# untitled_5.net
KiCad netlist of a schematic drawn in EAGLE
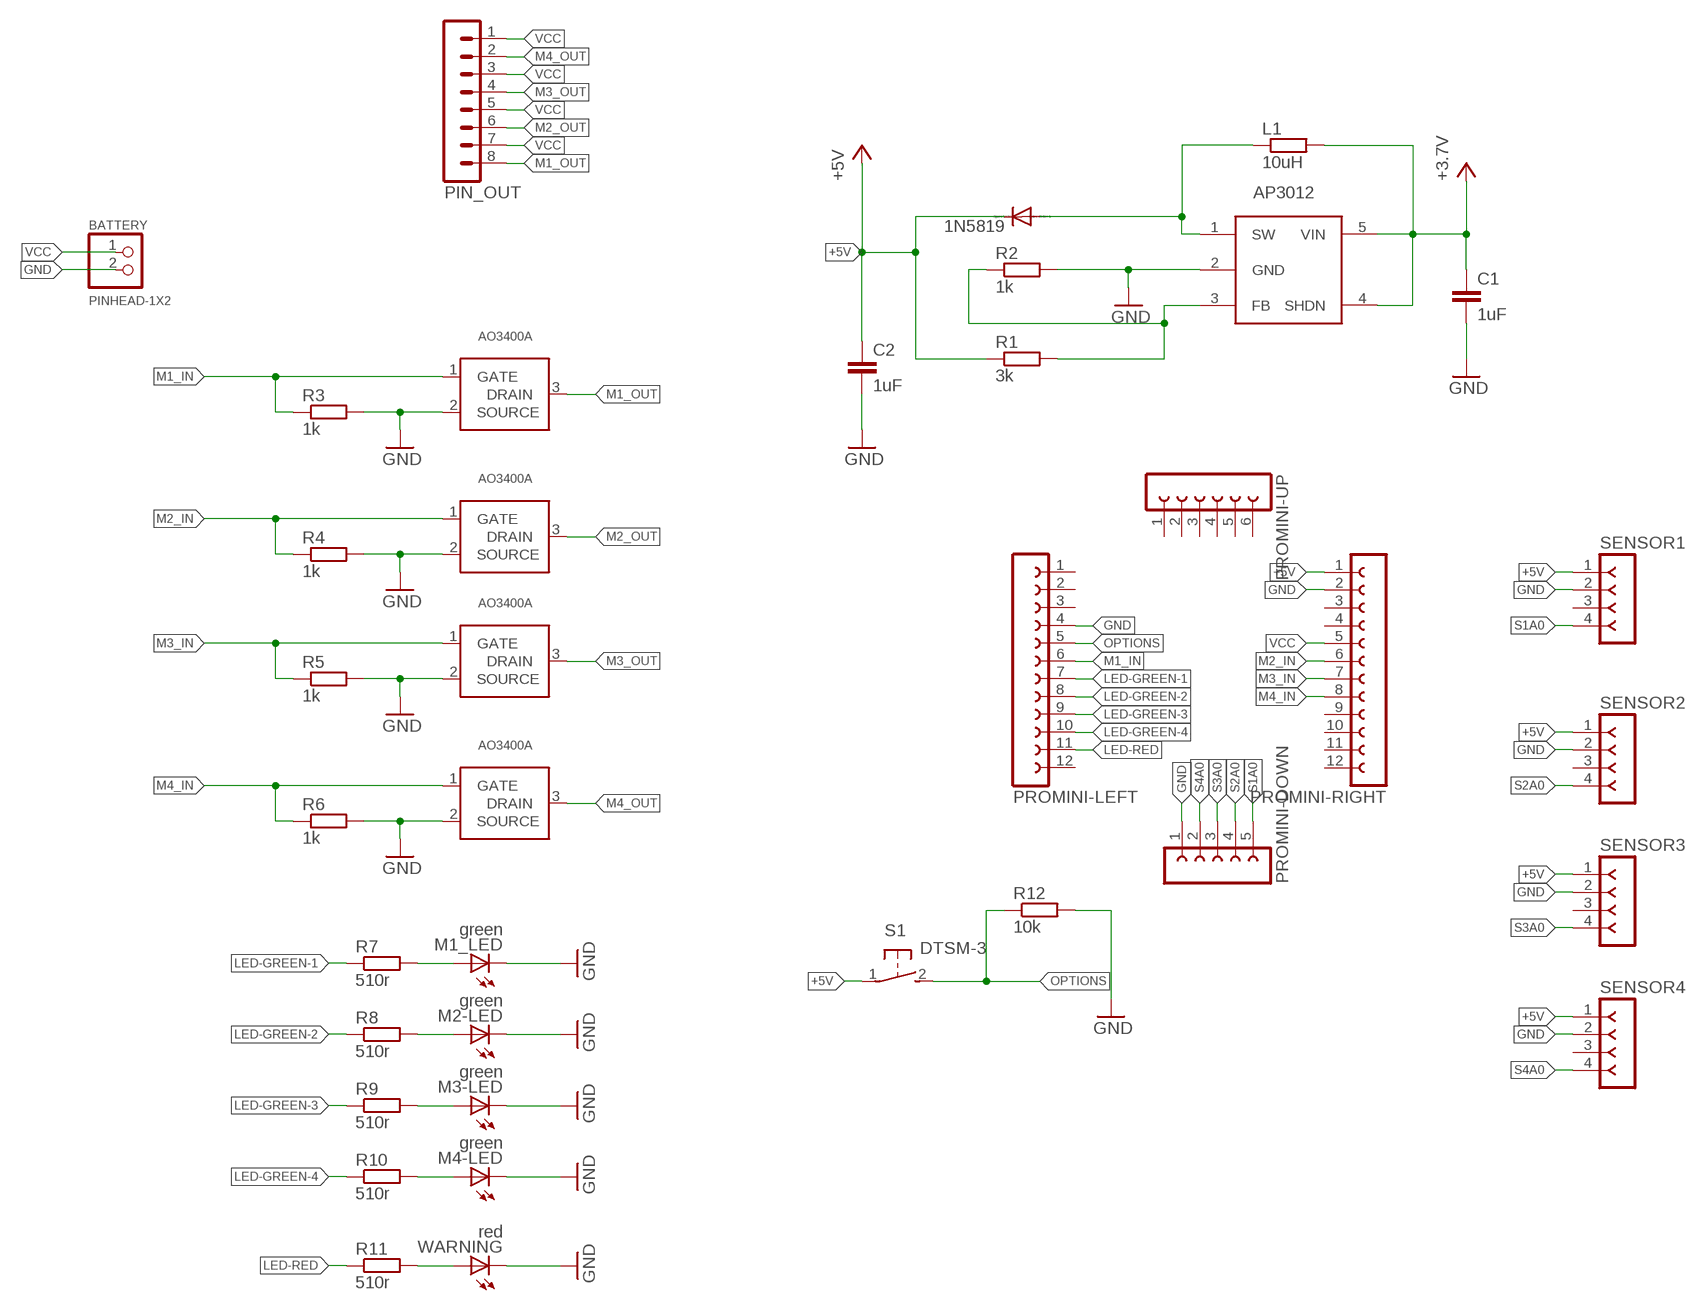
[diagram p0: schematic, sheet 1]

(export (version "E")
  (design (tool "Eeschema 10.0.6"))
  (components
    (comp (ref "1N5819")
      (value "DIODE-DO214AC")
      (footprint "eagle-import:DO214AC")
      (libsource (lib "eagle-import") (part "DIODE-DO214AC"))
    )
    (comp (ref "BATTERY")
      (value "PINHEAD-1X2")
      (footprint "eagle-import:PIHEAD-1X2")
      (libsource (lib "eagle-import") (part "PINHEAD-1X2"))
    )
    (comp (ref "C1")
      (value "1uF")
      (footprint "eagle-import:C1206")
      (libsource (lib "eagle-import") (part "C-EUC1206"))
    )
    (comp (ref "C2")
      (value "1uF")
      (footprint "eagle-import:C1206")
      (libsource (lib "eagle-import") (part "C-EUC1206"))
    )
    (comp (ref "L1")
      (value "10uH")
      (footprint "eagle-import:R0805")
      (libsource (lib "eagle-import") (part "R-EU_R0805"))
    )
    (comp (ref "M1_LED")
      (value "green")
      (footprint "eagle-import:CHIP-LED0805")
      (libsource (lib "eagle-import") (part "LEDCHIP-LED0805"))
    )
    (comp (ref "M2-LED")
      (value "green")
      (footprint "eagle-import:CHIP-LED0805")
      (libsource (lib "eagle-import") (part "LEDCHIP-LED0805"))
    )
    (comp (ref "M3-LED")
      (value "green")
      (footprint "eagle-import:CHIP-LED0805")
      (libsource (lib "eagle-import") (part "LEDCHIP-LED0805"))
    )
    (comp (ref "M4-LED")
      (value "green")
      (footprint "eagle-import:CHIP-LED0805")
      (libsource (lib "eagle-import") (part "LEDCHIP-LED0805"))
    )
    (comp (ref "MOSFET1")
      (value "AO3400A")
      (footprint "eagle-import:SOT-23")
      (libsource (lib "eagle-import") (part "AO3400A"))
    )
    (comp (ref "MOSFET2")
      (value "AO3400A")
      (footprint "eagle-import:SOT-23")
      (libsource (lib "eagle-import") (part "AO3400A"))
    )
    (comp (ref "MOSFET3")
      (value "AO3400A")
      (footprint "eagle-import:SOT-23")
      (libsource (lib "eagle-import") (part "AO3400A"))
    )
    (comp (ref "MOSFET4")
      (value "AO3400A")
      (footprint "eagle-import:SOT-23")
      (libsource (lib "eagle-import") (part "AO3400A"))
    )
    (comp (ref "PIN_OUT")
      (value "MA08-1")
      (footprint "eagle-import:MA08-1")
      (libsource (lib "eagle-import") (part "MA08-1"))
    )
    (comp (ref "PROMINI-DOWN")
      (value "FE05-1")
      (footprint "eagle-import:FE05-1")
      (libsource (lib "eagle-import") (part "FE05-1"))
    )
    (comp (ref "PROMINI-LEFT")
      (value "FE12-1")
      (footprint "eagle-import:FE12")
      (libsource (lib "eagle-import") (part "FE12-1"))
    )
    (comp (ref "PROMINI-RIGHT")
      (value "FE12-1")
      (footprint "eagle-import:FE12")
      (libsource (lib "eagle-import") (part "FE12-1"))
    )
    (comp (ref "PROMINI-UP")
      (value "FE06-1")
      (footprint "eagle-import:FE06")
      (libsource (lib "eagle-import") (part "FE06-1"))
    )
    (comp (ref "R1")
      (value "3k")
      (footprint "eagle-import:R1206")
      (libsource (lib "eagle-import") (part "R-EU_R1206"))
    )
    (comp (ref "R2")
      (value "1k")
      (footprint "eagle-import:R1206")
      (libsource (lib "eagle-import") (part "R-EU_R1206"))
    )
    (comp (ref "R3")
      (value "1k")
      (footprint "eagle-import:R1206")
      (libsource (lib "eagle-import") (part "R-EU_R1206"))
    )
    (comp (ref "R4")
      (value "1k")
      (footprint "eagle-import:R1206")
      (libsource (lib "eagle-import") (part "R-EU_R1206"))
    )
    (comp (ref "R5")
      (value "1k")
      (footprint "eagle-import:R1206")
      (libsource (lib "eagle-import") (part "R-EU_R1206"))
    )
    (comp (ref "R6")
      (value "1k")
      (footprint "eagle-import:R1206")
      (libsource (lib "eagle-import") (part "R-EU_R1206"))
    )
    (comp (ref "R7")
      (value "510r")
      (footprint "eagle-import:M0805")
      (libsource (lib "eagle-import") (part "R-EU_M0805"))
    )
    (comp (ref "R8")
      (value "510r")
      (footprint "eagle-import:M0805")
      (libsource (lib "eagle-import") (part "R-EU_M0805"))
    )
    (comp (ref "R9")
      (value "510r")
      (footprint "eagle-import:M0805")
      (libsource (lib "eagle-import") (part "R-EU_M0805"))
    )
    (comp (ref "R10")
      (value "510r")
      (footprint "eagle-import:M0805")
      (libsource (lib "eagle-import") (part "R-EU_M0805"))
    )
    (comp (ref "R11")
      (value "510r")
      (footprint "eagle-import:M0805")
      (libsource (lib "eagle-import") (part "R-EU_M0805"))
    )
    (comp (ref "R12")
      (value "10k")
      (footprint "eagle-import:R1206")
      (libsource (lib "eagle-import") (part "R-EU_R1206"))
    )
    (comp (ref "S1")
      (value "DTSM-3")
      (footprint "eagle-import:DTSM-3")
      (libsource (lib "eagle-import") (part "DTSM-3"))
    )
    (comp (ref "SENSOR1")
      (value "F-1X04-SIP-100-32Y")
      (footprint "eagle-import:SIP-100-04-32Y")
      (libsource (lib "eagle-import") (part "F-1X04-SIP-100-32Y"))
    )
    (comp (ref "SENSOR2")
      (value "F-1X04-SIP-100-32Y")
      (footprint "eagle-import:SIP-100-04-32Y")
      (libsource (lib "eagle-import") (part "F-1X04-SIP-100-32Y"))
    )
    (comp (ref "SENSOR3")
      (value "F-1X04-SIP-100-32Y")
      (footprint "eagle-import:SIP-100-04-32Y")
      (libsource (lib "eagle-import") (part "F-1X04-SIP-100-32Y"))
    )
    (comp (ref "SENSOR4")
      (value "F-1X04-SIP-100-32Y")
      (footprint "eagle-import:SIP-100-04-32Y")
      (libsource (lib "eagle-import") (part "F-1X04-SIP-100-32Y"))
    )
    (comp (ref "U$1")
      (value "AP3012")
      (footprint "eagle-import:SOT-23-5")
      (libsource (lib "eagle-import") (part "AP3012"))
    )
    (comp (ref "WARNING")
      (value "red")
      (footprint "eagle-import:CHIP-LED0805")
      (libsource (lib "eagle-import") (part "LEDCHIP-LED0805"))
    )
  )
  (nets
    (net (code "1") (name "+5V") (class "Default")
      (node (ref "1N5819") (pin "C") (pinfunction "C_C") (pintype "passive"))
      (node (ref "C2") (pin "1") (pinfunction "1_1") (pintype "passive"))
      (node (ref "PROMINI-RIGHT") (pin "1") (pinfunction "1_1") (pintype "passive"))
      (node (ref "R1") (pin "1") (pinfunction "1_1") (pintype "passive"))
      (node (ref "S1") (pin "1") (pinfunction "1_1") (pintype "passive"))
      (node (ref "SENSOR1") (pin "1") (pinfunction "1_1") (pintype "passive"))
      (node (ref "SENSOR2") (pin "1") (pinfunction "1_1") (pintype "passive"))
      (node (ref "SENSOR3") (pin "1") (pinfunction "1_1") (pintype "passive"))
      (node (ref "SENSOR4") (pin "1") (pinfunction "1_1") (pintype "passive"))
    )
    (net (code "2") (name "GND") (class "Default")
      (node (ref "BATTERY") (pin "2") (pinfunction "2_2") (pintype "passive"))
      (node (ref "C1") (pin "2") (pinfunction "2_2") (pintype "passive"))
      (node (ref "C2") (pin "2") (pinfunction "2_2") (pintype "passive"))
      (node (ref "M1_LED") (pin "C") (pinfunction "C_C") (pintype "passive"))
      (node (ref "M2-LED") (pin "C") (pinfunction "C_C") (pintype "passive"))
      (node (ref "M3-LED") (pin "C") (pinfunction "C_C") (pintype "passive"))
      (node (ref "M4-LED") (pin "C") (pinfunction "C_C") (pintype "passive"))
      (node (ref "MOSFET1") (pin "2") (pinfunction "SOURCE_2") (pintype "bidirectional"))
      (node (ref "MOSFET2") (pin "2") (pinfunction "SOURCE_2") (pintype "bidirectional"))
      (node (ref "MOSFET3") (pin "2") (pinfunction "SOURCE_2") (pintype "bidirectional"))
      (node (ref "MOSFET4") (pin "2") (pinfunction "SOURCE_2") (pintype "bidirectional"))
      (node (ref "PROMINI-DOWN") (pin "1") (pinfunction "1_1") (pintype "passive"))
      (node (ref "PROMINI-LEFT") (pin "4") (pinfunction "4_4") (pintype "passive"))
      (node (ref "PROMINI-RIGHT") (pin "2") (pinfunction "2_2") (pintype "passive"))
      (node (ref "R12") (pin "2") (pinfunction "2_2") (pintype "passive"))
      (node (ref "R2") (pin "2") (pinfunction "2_2") (pintype "passive"))
      (node (ref "R3") (pin "2") (pinfunction "2_2") (pintype "passive"))
      (node (ref "R4") (pin "2") (pinfunction "2_2") (pintype "passive"))
      (node (ref "R5") (pin "2") (pinfunction "2_2") (pintype "passive"))
      (node (ref "R6") (pin "2") (pinfunction "2_2") (pintype "passive"))
      (node (ref "SENSOR1") (pin "2") (pinfunction "2_2") (pintype "passive"))
      (node (ref "SENSOR2") (pin "2") (pinfunction "2_2") (pintype "passive"))
      (node (ref "SENSOR3") (pin "2") (pinfunction "2_2") (pintype "passive"))
      (node (ref "SENSOR4") (pin "2") (pinfunction "2_2") (pintype "passive"))
      (node (ref "U$1") (pin "2") (pinfunction "GND_2") (pintype "bidirectional"))
      (node (ref "WARNING") (pin "C") (pinfunction "C_C") (pintype "passive"))
    )
    (net (code "3") (name "LED-GREEN-1") (class "Default")
      (node (ref "PROMINI-LEFT") (pin "7") (pinfunction "7_7") (pintype "passive"))
      (node (ref "R7") (pin "1") (pinfunction "1_1") (pintype "passive"))
    )
    (net (code "4") (name "LED-GREEN-2") (class "Default")
      (node (ref "PROMINI-LEFT") (pin "8") (pinfunction "8_8") (pintype "passive"))
      (node (ref "R8") (pin "1") (pinfunction "1_1") (pintype "passive"))
    )
    (net (code "5") (name "LED-GREEN-3") (class "Default")
      (node (ref "PROMINI-LEFT") (pin "9") (pinfunction "9_9") (pintype "passive"))
      (node (ref "R9") (pin "1") (pinfunction "1_1") (pintype "passive"))
    )
    (net (code "6") (name "LED-GREEN-4") (class "Default")
      (node (ref "PROMINI-LEFT") (pin "10") (pinfunction "10_10") (pintype "passive"))
      (node (ref "R10") (pin "1") (pinfunction "1_1") (pintype "passive"))
    )
    (net (code "7") (name "LED-RED") (class "Default")
      (node (ref "PROMINI-LEFT") (pin "11") (pinfunction "11_11") (pintype "passive"))
      (node (ref "R11") (pin "1") (pinfunction "1_1") (pintype "passive"))
    )
    (net (code "8") (name "M1_IN") (class "Default")
      (node (ref "MOSFET1") (pin "1") (pinfunction "GATE_1") (pintype "bidirectional"))
      (node (ref "PROMINI-LEFT") (pin "6") (pinfunction "6_6") (pintype "passive"))
      (node (ref "R3") (pin "1") (pinfunction "1_1") (pintype "passive"))
    )
    (net (code "9") (name "M1_OUT") (class "Default")
      (node (ref "MOSFET1") (pin "3") (pinfunction "DRAIN_3") (pintype "bidirectional"))
      (node (ref "PIN_OUT") (pin "8") (pinfunction "8_8") (pintype "passive"))
    )
    (net (code "10") (name "M2_IN") (class "Default")
      (node (ref "MOSFET2") (pin "1") (pinfunction "GATE_1") (pintype "bidirectional"))
      (node (ref "PROMINI-RIGHT") (pin "6") (pinfunction "6_6") (pintype "passive"))
      (node (ref "R4") (pin "1") (pinfunction "1_1") (pintype "passive"))
    )
    (net (code "11") (name "M2_OUT") (class "Default")
      (node (ref "MOSFET2") (pin "3") (pinfunction "DRAIN_3") (pintype "bidirectional"))
      (node (ref "PIN_OUT") (pin "6") (pinfunction "6_6") (pintype "passive"))
    )
    (net (code "12") (name "M3_IN") (class "Default")
      (node (ref "MOSFET3") (pin "1") (pinfunction "GATE_1") (pintype "bidirectional"))
      (node (ref "PROMINI-RIGHT") (pin "7") (pinfunction "7_7") (pintype "passive"))
      (node (ref "R5") (pin "1") (pinfunction "1_1") (pintype "passive"))
    )
    (net (code "13") (name "M3_OUT") (class "Default")
      (node (ref "MOSFET3") (pin "3") (pinfunction "DRAIN_3") (pintype "bidirectional"))
      (node (ref "PIN_OUT") (pin "4") (pinfunction "4_4") (pintype "passive"))
    )
    (net (code "14") (name "M4_IN") (class "Default")
      (node (ref "MOSFET4") (pin "1") (pinfunction "GATE_1") (pintype "bidirectional"))
      (node (ref "PROMINI-RIGHT") (pin "8") (pinfunction "8_8") (pintype "passive"))
      (node (ref "R6") (pin "1") (pinfunction "1_1") (pintype "passive"))
    )
    (net (code "15") (name "M4_OUT") (class "Default")
      (node (ref "MOSFET4") (pin "3") (pinfunction "DRAIN_3") (pintype "bidirectional"))
      (node (ref "PIN_OUT") (pin "2") (pinfunction "2_2") (pintype "passive"))
    )
    (net (code "16") (name "Net-(M1_LED-PadA)") (class "Default")
      (node (ref "M1_LED") (pin "A") (pinfunction "A_A") (pintype "passive"))
      (node (ref "R7") (pin "2") (pinfunction "2_2") (pintype "passive"))
    )
    (net (code "17") (name "Net-(M2-LED-PadA)") (class "Default")
      (node (ref "M2-LED") (pin "A") (pinfunction "A_A") (pintype "passive"))
      (node (ref "R8") (pin "2") (pinfunction "2_2") (pintype "passive"))
    )
    (net (code "18") (name "Net-(M3-LED-PadA)") (class "Default")
      (node (ref "M3-LED") (pin "A") (pinfunction "A_A") (pintype "passive"))
      (node (ref "R9") (pin "2") (pinfunction "2_2") (pintype "passive"))
    )
    (net (code "19") (name "Net-(M4-LED-PadA)") (class "Default")
      (node (ref "M4-LED") (pin "A") (pinfunction "A_A") (pintype "passive"))
      (node (ref "R10") (pin "2") (pinfunction "2_2") (pintype "passive"))
    )
    (net (code "20") (name "Net-(R11-Pad2)") (class "Default")
      (node (ref "R11") (pin "2") (pinfunction "2_2") (pintype "passive"))
      (node (ref "WARNING") (pin "A") (pinfunction "A_A") (pintype "passive"))
    )
    (net (code "21") (name "Net-(U$1-FB)") (class "Default")
      (node (ref "R1") (pin "2") (pinfunction "2_2") (pintype "passive"))
      (node (ref "R2") (pin "1") (pinfunction "1_1") (pintype "passive"))
      (node (ref "U$1") (pin "3") (pinfunction "FB_3") (pintype "bidirectional"))
    )
    (net (code "22") (name "Net-(U$1-SW)") (class "Default")
      (node (ref "1N5819") (pin "A") (pinfunction "A_A") (pintype "passive"))
      (node (ref "L1") (pin "1") (pinfunction "1_1") (pintype "passive"))
      (node (ref "U$1") (pin "1") (pinfunction "SW_1") (pintype "bidirectional"))
    )
    (net (code "23") (name "OPTIONS") (class "Default")
      (node (ref "PROMINI-LEFT") (pin "5") (pinfunction "5_5") (pintype "passive"))
      (node (ref "R12") (pin "1") (pinfunction "1_1") (pintype "passive"))
      (node (ref "S1") (pin "2") (pinfunction "2_2") (pintype "passive"))
    )
    (net (code "24") (name "S1A0") (class "Default")
      (node (ref "PROMINI-DOWN") (pin "5") (pinfunction "5_5") (pintype "passive"))
      (node (ref "SENSOR1") (pin "4") (pinfunction "4_4") (pintype "passive"))
    )
    (net (code "25") (name "S2A0") (class "Default")
      (node (ref "PROMINI-DOWN") (pin "4") (pinfunction "4_4") (pintype "passive"))
      (node (ref "SENSOR2") (pin "4") (pinfunction "4_4") (pintype "passive"))
    )
    (net (code "26") (name "S3A0") (class "Default")
      (node (ref "PROMINI-DOWN") (pin "3") (pinfunction "3_3") (pintype "passive"))
      (node (ref "SENSOR3") (pin "4") (pinfunction "4_4") (pintype "passive"))
    )
    (net (code "27") (name "S4A0") (class "Default")
      (node (ref "PROMINI-DOWN") (pin "2") (pinfunction "2_2") (pintype "passive"))
      (node (ref "SENSOR4") (pin "4") (pinfunction "4_4") (pintype "passive"))
    )
    (net (code "28") (name "VCC") (class "Default")
      (node (ref "BATTERY") (pin "1") (pinfunction "1_1") (pintype "passive"))
      (node (ref "C1") (pin "1") (pinfunction "1_1") (pintype "passive"))
      (node (ref "L1") (pin "2") (pinfunction "2_2") (pintype "passive"))
      (node (ref "PIN_OUT") (pin "1") (pinfunction "1_1") (pintype "passive"))
      (node (ref "PIN_OUT") (pin "3") (pinfunction "3_3") (pintype "passive"))
      (node (ref "PIN_OUT") (pin "5") (pinfunction "5_5") (pintype "passive"))
      (node (ref "PIN_OUT") (pin "7") (pinfunction "7_7") (pintype "passive"))
      (node (ref "PROMINI-RIGHT") (pin "5") (pinfunction "5_5") (pintype "passive"))
      (node (ref "U$1") (pin "4") (pinfunction "SHDN_4") (pintype "bidirectional"))
      (node (ref "U$1") (pin "5") (pinfunction "VIN_5") (pintype "bidirectional"))
    )
    (net (code "29") (name "unconnected-(PROMINI-LEFT-Pad1)") (class "Default")
      (node (ref "PROMINI-LEFT") (pin "1") (pinfunction "1_1") (pintype "passive"))
    )
    (net (code "30") (name "unconnected-(PROMINI-LEFT-Pad2)") (class "Default")
      (node (ref "PROMINI-LEFT") (pin "2") (pinfunction "2_2") (pintype "passive"))
    )
    (net (code "31") (name "unconnected-(PROMINI-LEFT-Pad3)") (class "Default")
      (node (ref "PROMINI-LEFT") (pin "3") (pinfunction "3_3") (pintype "passive"))
    )
    (net (code "32") (name "unconnected-(PROMINI-LEFT-Pad12)") (class "Default")
      (node (ref "PROMINI-LEFT") (pin "12") (pinfunction "12_12") (pintype "passive"))
    )
    (net (code "33") (name "unconnected-(PROMINI-RIGHT-Pad3)") (class "Default")
      (node (ref "PROMINI-RIGHT") (pin "3") (pinfunction "3_3") (pintype "passive"))
    )
    (net (code "34") (name "unconnected-(PROMINI-RIGHT-Pad4)") (class "Default")
      (node (ref "PROMINI-RIGHT") (pin "4") (pinfunction "4_4") (pintype "passive"))
    )
    (net (code "35") (name "unconnected-(PROMINI-RIGHT-Pad9)") (class "Default")
      (node (ref "PROMINI-RIGHT") (pin "9") (pinfunction "9_9") (pintype "passive"))
    )
    (net (code "36") (name "unconnected-(PROMINI-RIGHT-Pad10)") (class "Default")
      (node (ref "PROMINI-RIGHT") (pin "10") (pinfunction "10_10") (pintype "passive"))
    )
    (net (code "37") (name "unconnected-(PROMINI-RIGHT-Pad11)") (class "Default")
      (node (ref "PROMINI-RIGHT") (pin "11") (pinfunction "11_11") (pintype "passive"))
    )
    (net (code "38") (name "unconnected-(PROMINI-RIGHT-Pad12)") (class "Default")
      (node (ref "PROMINI-RIGHT") (pin "12") (pinfunction "12_12") (pintype "passive"))
    )
    (net (code "39") (name "unconnected-(PROMINI-UP-Pad1)") (class "Default")
      (node (ref "PROMINI-UP") (pin "1") (pinfunction "1_1") (pintype "passive"))
    )
    (net (code "40") (name "unconnected-(PROMINI-UP-Pad2)") (class "Default")
      (node (ref "PROMINI-UP") (pin "2") (pinfunction "2_2") (pintype "passive"))
    )
    (net (code "41") (name "unconnected-(PROMINI-UP-Pad3)") (class "Default")
      (node (ref "PROMINI-UP") (pin "3") (pinfunction "3_3") (pintype "passive"))
    )
    (net (code "42") (name "unconnected-(PROMINI-UP-Pad4)") (class "Default")
      (node (ref "PROMINI-UP") (pin "4") (pinfunction "4_4") (pintype "passive"))
    )
    (net (code "43") (name "unconnected-(PROMINI-UP-Pad5)") (class "Default")
      (node (ref "PROMINI-UP") (pin "5") (pinfunction "5_5") (pintype "passive"))
    )
    (net (code "44") (name "unconnected-(PROMINI-UP-Pad6)") (class "Default")
      (node (ref "PROMINI-UP") (pin "6") (pinfunction "6_6") (pintype "passive"))
    )
    (net (code "45") (name "unconnected-(SENSOR1-Pad3)") (class "Default")
      (node (ref "SENSOR1") (pin "3") (pinfunction "3_3") (pintype "passive"))
    )
    (net (code "46") (name "unconnected-(SENSOR2-Pad3)") (class "Default")
      (node (ref "SENSOR2") (pin "3") (pinfunction "3_3") (pintype "passive"))
    )
    (net (code "47") (name "unconnected-(SENSOR3-Pad3)") (class "Default")
      (node (ref "SENSOR3") (pin "3") (pinfunction "3_3") (pintype "passive"))
    )
    (net (code "48") (name "unconnected-(SENSOR4-Pad3)") (class "Default")
      (node (ref "SENSOR4") (pin "3") (pinfunction "3_3") (pintype "passive"))
    )
  )
)
